# FemtoI2C.net
KiCad netlist of a schematic drawn in EAGLE
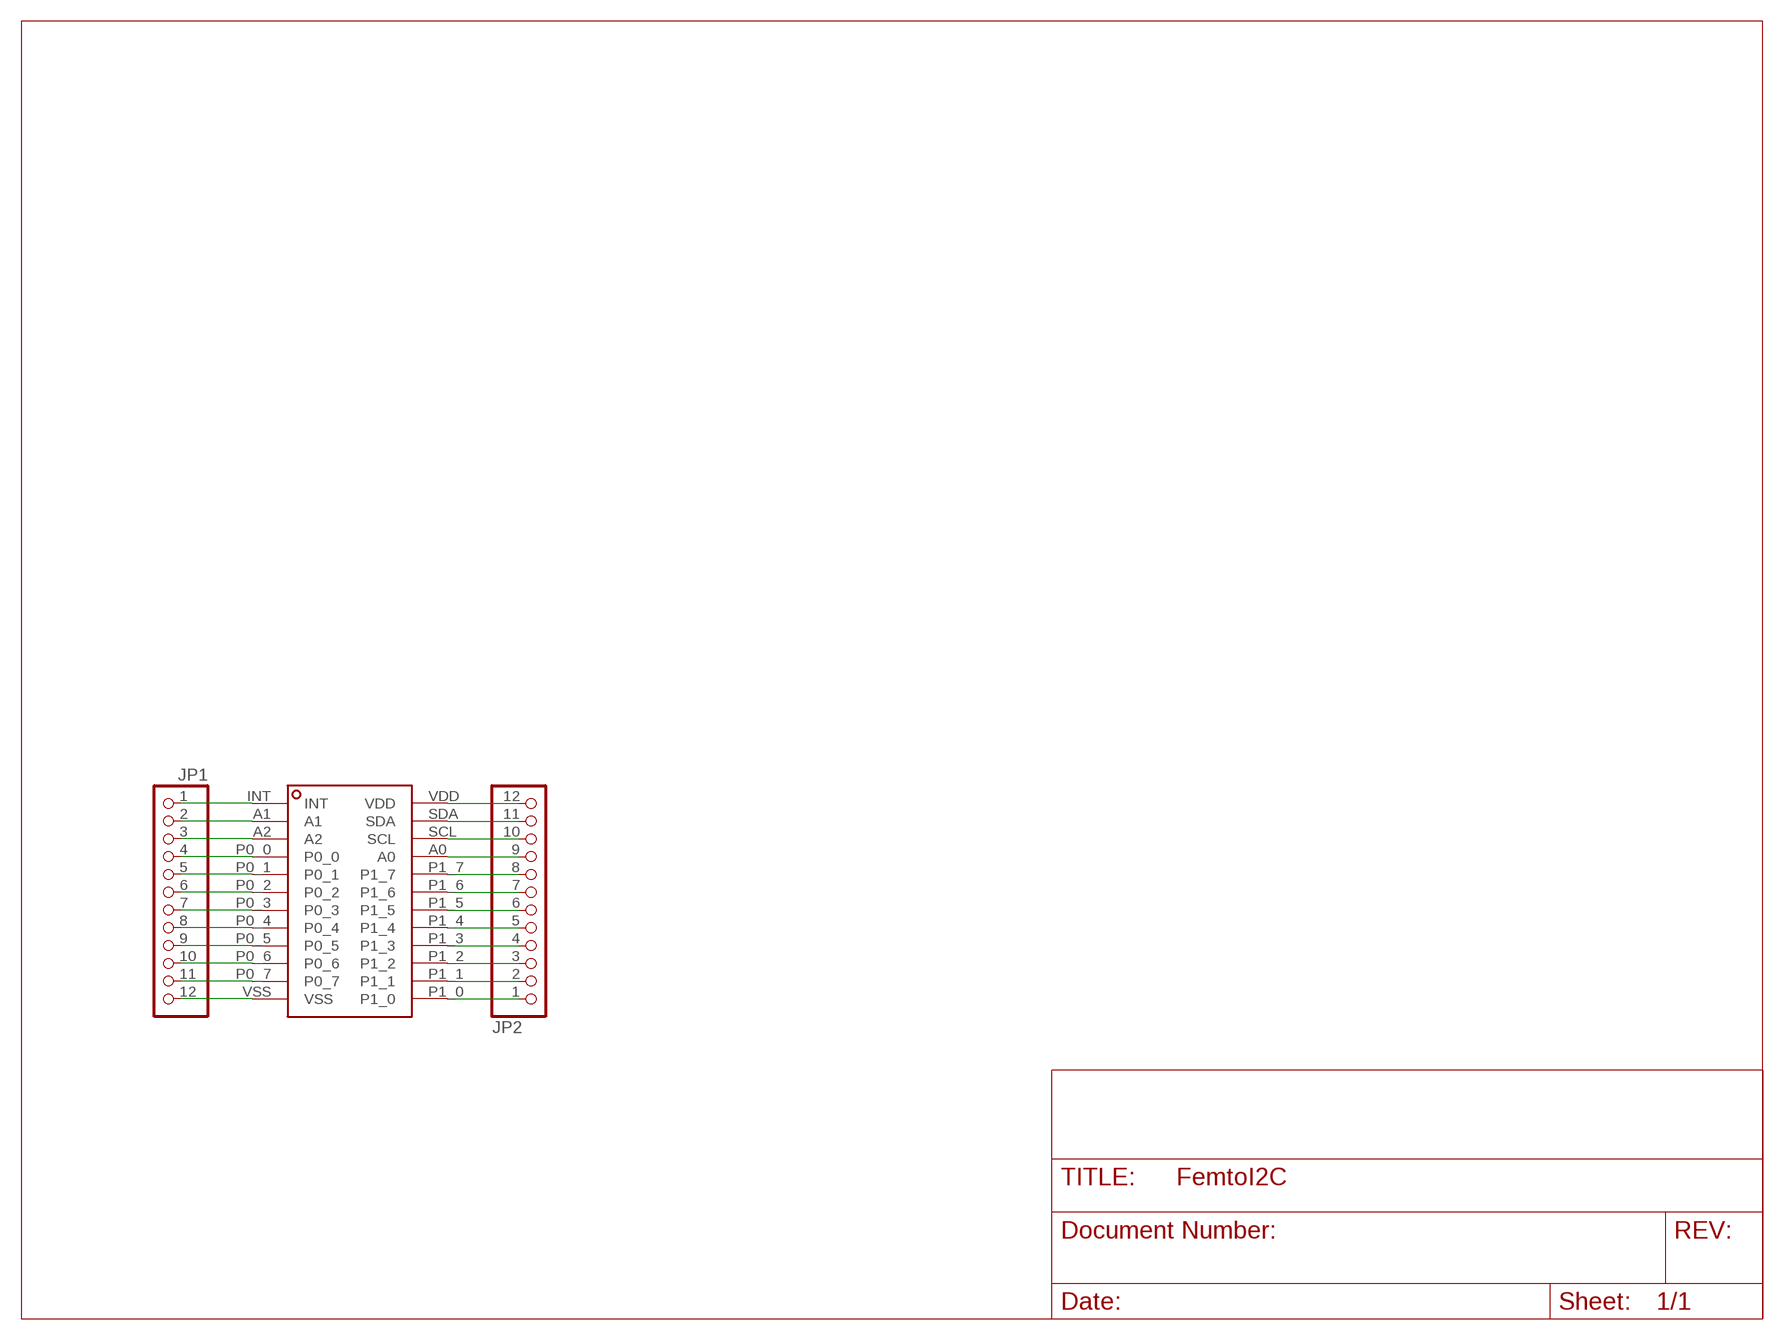
[diagram p0: schematic, sheet 1]

(export (version "E")
  (design (tool "Eeschema 10.0.6"))
  (components
    (comp (ref "JP1")
      (value "PINHD-1X12")
      (footprint "eagle-import:1X12")
      (libsource (lib "eagle-import") (part "PINHD-1X12"))
    )
    (comp (ref "JP2")
      (value "PINHD-1X12")
      (footprint "eagle-import:1X12")
      (libsource (lib "eagle-import") (part "PINHD-1X12"))
    )
    (comp (ref "U$1")
      (value "PCA9555A_TSSOP24")
      (footprint "eagle-import:PCA9555A_TSSOP24")
      (libsource (lib "eagle-import") (part "PCA9555A_TSSOP24"))
    )
  )
  (nets
    (net (code "1") (name "Net-(JP1-Pad1)") (class "Default")
      (node (ref "JP1") (pin "1") (pinfunction "1_1") (pintype "passive"))
      (node (ref "U$1") (pin "INT") (pinfunction "INT_INT") (pintype "bidirectional"))
    )
    (net (code "2") (name "Net-(JP1-Pad2)") (class "Default")
      (node (ref "JP1") (pin "2") (pinfunction "2_2") (pintype "passive"))
      (node (ref "U$1") (pin "A1") (pinfunction "A1_A1") (pintype "bidirectional"))
    )
    (net (code "3") (name "Net-(JP1-Pad3)") (class "Default")
      (node (ref "JP1") (pin "3") (pinfunction "3_3") (pintype "passive"))
      (node (ref "U$1") (pin "A2") (pinfunction "A2_A2") (pintype "bidirectional"))
    )
    (net (code "4") (name "Net-(JP1-Pad4)") (class "Default")
      (node (ref "JP1") (pin "4") (pinfunction "4_4") (pintype "passive"))
      (node (ref "U$1") (pin "P0_0") (pinfunction "P0_0_P0_0") (pintype "bidirectional"))
    )
    (net (code "5") (name "Net-(JP1-Pad5)") (class "Default")
      (node (ref "JP1") (pin "5") (pinfunction "5_5") (pintype "passive"))
      (node (ref "U$1") (pin "P0_1") (pinfunction "P0_1_P0_1") (pintype "bidirectional"))
    )
    (net (code "6") (name "Net-(JP1-Pad6)") (class "Default")
      (node (ref "JP1") (pin "6") (pinfunction "6_6") (pintype "passive"))
      (node (ref "U$1") (pin "P0_2") (pinfunction "P0_2_P0_2") (pintype "bidirectional"))
    )
    (net (code "7") (name "Net-(JP1-Pad7)") (class "Default")
      (node (ref "JP1") (pin "7") (pinfunction "7_7") (pintype "passive"))
      (node (ref "U$1") (pin "P0_3") (pinfunction "P0_3_P0_3") (pintype "bidirectional"))
    )
    (net (code "8") (name "Net-(JP1-Pad8)") (class "Default")
      (node (ref "JP1") (pin "8") (pinfunction "8_8") (pintype "passive"))
      (node (ref "U$1") (pin "P0_4") (pinfunction "P0_4_P0_4") (pintype "bidirectional"))
    )
    (net (code "9") (name "Net-(JP1-Pad9)") (class "Default")
      (node (ref "JP1") (pin "9") (pinfunction "9_9") (pintype "passive"))
      (node (ref "U$1") (pin "P0_5") (pinfunction "P0_5_P0_5") (pintype "bidirectional"))
    )
    (net (code "10") (name "Net-(JP1-Pad10)") (class "Default")
      (node (ref "JP1") (pin "10") (pinfunction "10_10") (pintype "passive"))
      (node (ref "U$1") (pin "P0_6") (pinfunction "P0_6_P0_6") (pintype "bidirectional"))
    )
    (net (code "11") (name "Net-(JP1-Pad11)") (class "Default")
      (node (ref "JP1") (pin "11") (pinfunction "11_11") (pintype "passive"))
      (node (ref "U$1") (pin "P0_7") (pinfunction "P0_7_P0_7") (pintype "bidirectional"))
    )
    (net (code "12") (name "Net-(JP1-Pad12)") (class "Default")
      (node (ref "JP1") (pin "12") (pinfunction "12_12") (pintype "passive"))
      (node (ref "U$1") (pin "VSS") (pinfunction "VSS_VSS") (pintype "bidirectional"))
    )
    (net (code "13") (name "Net-(JP2-Pad1)") (class "Default")
      (node (ref "JP2") (pin "1") (pinfunction "1_1") (pintype "passive"))
      (node (ref "U$1") (pin "P1_0") (pinfunction "P1_0_P1_0") (pintype "bidirectional"))
    )
    (net (code "14") (name "Net-(JP2-Pad2)") (class "Default")
      (node (ref "JP2") (pin "2") (pinfunction "2_2") (pintype "passive"))
      (node (ref "U$1") (pin "P1_1") (pinfunction "P1_1_P1_1") (pintype "bidirectional"))
    )
    (net (code "15") (name "Net-(JP2-Pad3)") (class "Default")
      (node (ref "JP2") (pin "3") (pinfunction "3_3") (pintype "passive"))
      (node (ref "U$1") (pin "P1_2") (pinfunction "P1_2_P1_2") (pintype "bidirectional"))
    )
    (net (code "16") (name "Net-(JP2-Pad4)") (class "Default")
      (node (ref "JP2") (pin "4") (pinfunction "4_4") (pintype "passive"))
      (node (ref "U$1") (pin "P1_3") (pinfunction "P1_3_P1_3") (pintype "bidirectional"))
    )
    (net (code "17") (name "Net-(JP2-Pad5)") (class "Default")
      (node (ref "JP2") (pin "5") (pinfunction "5_5") (pintype "passive"))
      (node (ref "U$1") (pin "P1_4") (pinfunction "P1_4_P1_4") (pintype "bidirectional"))
    )
    (net (code "18") (name "Net-(JP2-Pad6)") (class "Default")
      (node (ref "JP2") (pin "6") (pinfunction "6_6") (pintype "passive"))
      (node (ref "U$1") (pin "P1_5") (pinfunction "P1_5_P1_5") (pintype "bidirectional"))
    )
    (net (code "19") (name "Net-(JP2-Pad7)") (class "Default")
      (node (ref "JP2") (pin "7") (pinfunction "7_7") (pintype "passive"))
      (node (ref "U$1") (pin "P1_6") (pinfunction "P1_6_P1_6") (pintype "bidirectional"))
    )
    (net (code "20") (name "Net-(JP2-Pad8)") (class "Default")
      (node (ref "JP2") (pin "8") (pinfunction "8_8") (pintype "passive"))
      (node (ref "U$1") (pin "P1_7") (pinfunction "P1_7_P1_7") (pintype "bidirectional"))
    )
    (net (code "21") (name "Net-(JP2-Pad9)") (class "Default")
      (node (ref "JP2") (pin "9") (pinfunction "9_9") (pintype "passive"))
      (node (ref "U$1") (pin "A0") (pinfunction "A0_A0") (pintype "bidirectional"))
    )
    (net (code "22") (name "Net-(JP2-Pad10)") (class "Default")
      (node (ref "JP2") (pin "10") (pinfunction "10_10") (pintype "passive"))
      (node (ref "U$1") (pin "SCL") (pinfunction "SCL_SCL") (pintype "bidirectional"))
    )
    (net (code "23") (name "Net-(JP2-Pad11)") (class "Default")
      (node (ref "JP2") (pin "11") (pinfunction "11_11") (pintype "passive"))
      (node (ref "U$1") (pin "SDA") (pinfunction "SDA_SDA") (pintype "bidirectional"))
    )
    (net (code "24") (name "Net-(JP2-Pad12)") (class "Default")
      (node (ref "JP2") (pin "12") (pinfunction "12_12") (pintype "passive"))
      (node (ref "U$1") (pin "VDD") (pinfunction "VDD_VDD") (pintype "bidirectional"))
    )
  )
)
